# Sheet1.net
KiCad netlist of a schematic drawn in Altium Designer
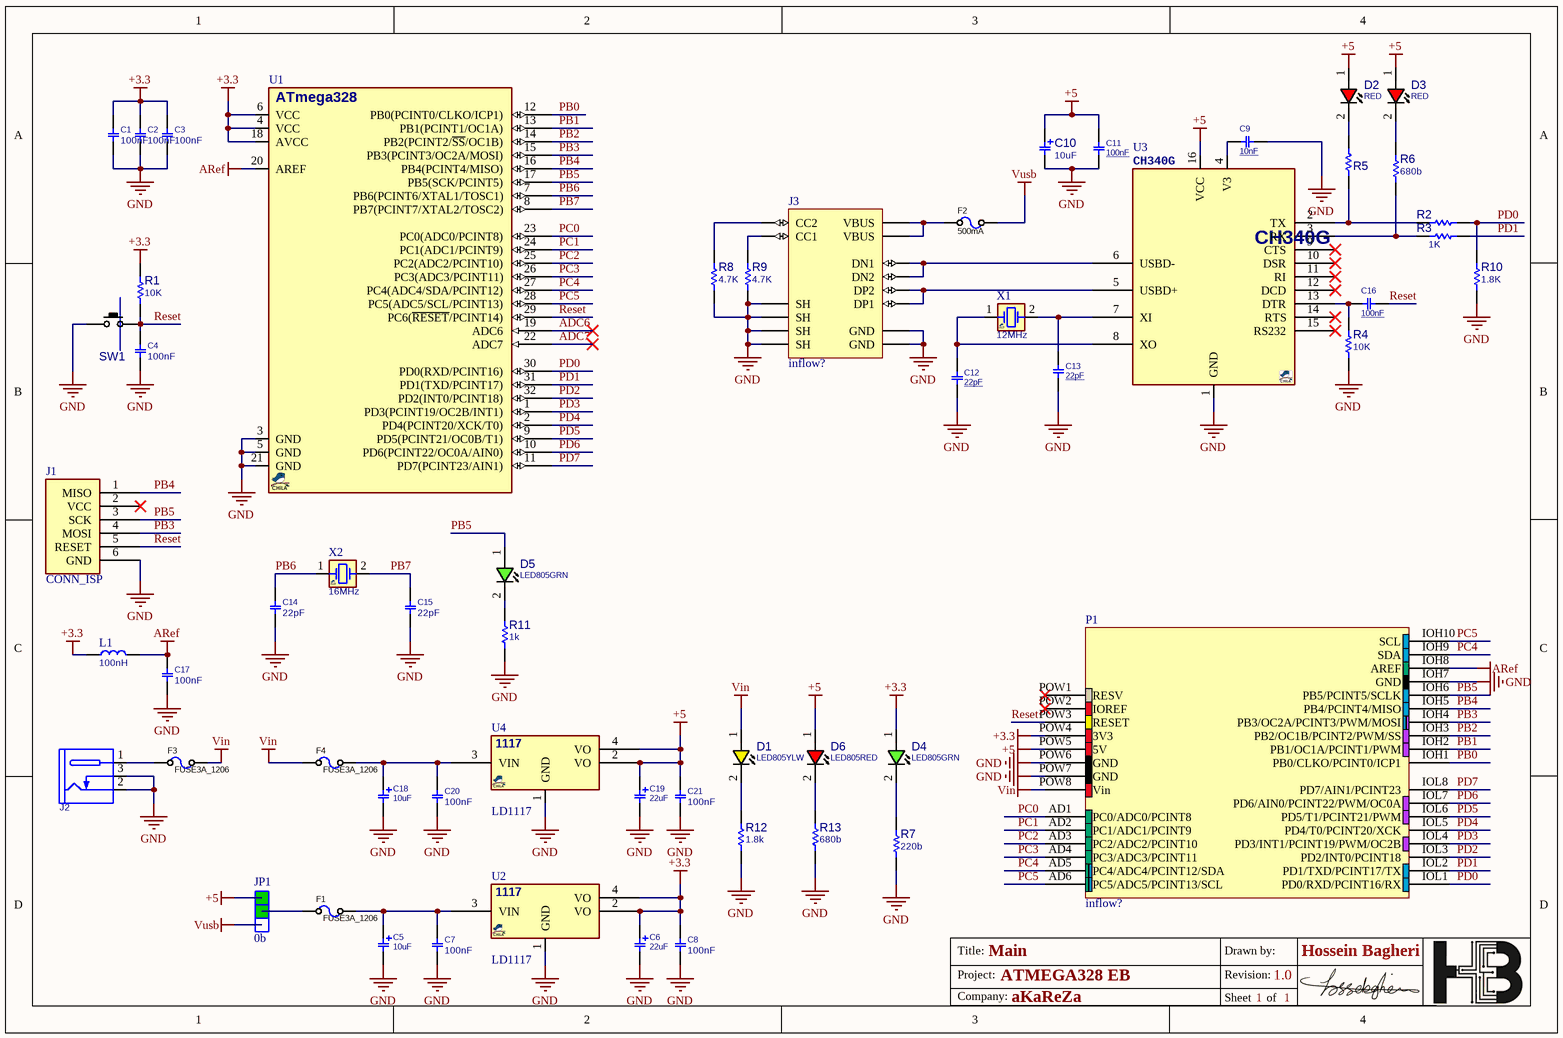
[diagram p0: Sheet1.SchDoc]

(export (version "E")
  (design (tool "Eeschema 10.0.6"))
  (components
    (comp (ref "C1")
      (value "100nF")
      (footprint "C0805")
      (description "CAP, MLCC")
      (fields (field (name "MANF_P#") "MANF_PART#"))
      (libsource (lib "Chila_PCB") (part "CAP_SMD_MLCC_0805"))
    )
    (comp (ref "C2")
      (value "100nF")
      (footprint "C0805")
      (description "CAP, MLCC")
      (fields (field (name "MANF_P#") "MANF_PART#"))
      (libsource (lib "Chila_PCB") (part "CAP_SMD_MLCC_0805"))
    )
    (comp (ref "C3")
      (value "100nF")
      (footprint "C0805")
      (description "CAP, MLCC")
      (fields (field (name "MANF_P#") "MANF_PART#"))
      (libsource (lib "Chila_PCB") (part "CAP_SMD_MLCC_0805"))
    )
    (comp (ref "C4")
      (value "100nF")
      (footprint "C0805")
      (description "CAP, MLCC")
      (fields (field (name "MANF_P#") "MANF_PART#"))
      (libsource (lib "Chila_PCB") (part "CAP_SMD_MLCC_0805"))
    )
    (comp (ref "C5")
      (value "10uF")
      (footprint "C_TN_2012")
      (description "CAP, SMD, TAN")
      (fields (field (name "MANF") "VISHAY") (field (name "MANF_P#") "T55A106M6R3C0300"))
      (libsource (lib "Chila_PCB") (part "CAP_SMD_TAN"))
    )
    (comp (ref "C6")
      (value "22uF")
      (footprint "C_TN_2012")
      (description "CAP, SMD, TAN")
      (fields (field (name "MANF") "VISHAY") (field (name "MANF_P#") "T55A106M6R3C0300"))
      (libsource (lib "Chila_PCB") (part "CAP_SMD_TAN"))
    )
    (comp (ref "C7")
      (value "100nF")
      (footprint "C1206")
      (description "CAP, MLCC")
      (fields (field (name "MANF_P#") "MANF_PART#"))
      (libsource (lib "Chila_PCB") (part "CAP_SMD_MLCC_1206"))
    )
    (comp (ref "C8")
      (value "100nF")
      (footprint "C1206")
      (description "CAP, MLCC")
      (fields (field (name "MANF_P#") "MANF_PART#"))
      (libsource (lib "Chila_PCB") (part "CAP_SMD_MLCC_1206"))
    )
    (comp (ref "C9")
      (value "10nF")
      (footprint "C1206")
      (description "CAP, FILM, 680nF, 16V, Acryl, 20%, 1206")
      (fields (field (name "MANF") "Murata"))
      (libsource (lib "Chila_PCB") (part "CAP_SMD_FILM"))
    )
    (comp (ref "C10")
      (value "10uF")
      (footprint "C_EL_D4L5")
      (description "CAP, SMD, ELEC,")
      (fields (field (name "MANF_P#") "MANF_PART#") (field (name "MANF") "MANF"))
      (libsource (lib "Chila_PCB") (part "CAP_SMD_EL"))
    )
    (comp (ref "C11")
      (value "100nF")
      (footprint "C1206")
      (description "CAP, FILM, 680nF, 16V, Acryl, 20%, 1206")
      (fields (field (name "MANF") "Murata"))
      (libsource (lib "Chila_PCB") (part "CAP_SMD_FILM"))
    )
    (comp (ref "C12")
      (value "22pF")
      (footprint "C1206")
      (description "CAP, FILM, 680nF, 16V, Acryl, 20%, 1206")
      (fields (field (name "MANF") "Murata"))
      (libsource (lib "Chila_PCB") (part "CAP_SMD_FILM"))
    )
    (comp (ref "C13")
      (value "22pF")
      (footprint "C1206")
      (description "CAP, FILM, 680nF, 16V, Acryl, 20%, 1206")
      (fields (field (name "MANF") "Murata"))
      (libsource (lib "Chila_PCB") (part "CAP_SMD_FILM"))
    )
    (comp (ref "C14")
      (value "22pF")
      (footprint "C0805")
      (description "CAP, MLCC")
      (fields (field (name "MANF_P#") "MANF_PART#"))
      (libsource (lib "Chila_PCB") (part "CAP_SMD_MLCC_0805"))
    )
    (comp (ref "C15")
      (value "22pF")
      (footprint "C0805")
      (description "CAP, MLCC")
      (fields (field (name "MANF_P#") "MANF_PART#"))
      (libsource (lib "Chila_PCB") (part "CAP_SMD_MLCC_0805"))
    )
    (comp (ref "C16")
      (value "100nF")
      (footprint "C1206")
      (description "CAP, FILM, 680nF, 16V, Acryl, 20%, 1206")
      (fields (field (name "MANF") "Murata"))
      (libsource (lib "Chila_PCB") (part "CAP_SMD_FILM"))
    )
    (comp (ref "C17")
      (value "100nF")
      (footprint "C0805")
      (description "CAP, MLCC")
      (fields (field (name "MANF_P#") "MANF_PART#"))
      (libsource (lib "Chila_PCB") (part "CAP_SMD_MLCC_0805"))
    )
    (comp (ref "C18")
      (value "10uF")
      (footprint "C_TN_2012")
      (description "CAP, SMD, TAN")
      (fields (field (name "MANF") "VISHAY") (field (name "MANF_P#") "T55A106M6R3C0300"))
      (libsource (lib "Chila_PCB") (part "CAP_SMD_TAN"))
    )
    (comp (ref "C19")
      (value "22uF")
      (footprint "C_TN_2012")
      (description "CAP, SMD, TAN")
      (fields (field (name "MANF") "VISHAY") (field (name "MANF_P#") "T55A106M6R3C0300"))
      (libsource (lib "Chila_PCB") (part "CAP_SMD_TAN"))
    )
    (comp (ref "C20")
      (value "100nF")
      (footprint "C1206")
      (description "CAP, MLCC")
      (fields (field (name "MANF_P#") "MANF_PART#"))
      (libsource (lib "Chila_PCB") (part "CAP_SMD_MLCC_1206"))
    )
    (comp (ref "C21")
      (value "100nF")
      (footprint "C1206")
      (description "CAP, MLCC")
      (fields (field (name "MANF_P#") "MANF_PART#"))
      (libsource (lib "Chila_PCB") (part "CAP_SMD_MLCC_1206"))
    )
    (comp (ref "D1")
      (value "LED805YLW")
      (footprint "LED0805YLW")
      (description "LED, SMD, 0805, YELLOW")
      (fields (field (name "MANF") "MANF") (field (name "MANF_P#") "MANF_PART#"))
      (libsource (lib "Chila_PCB") (part "LED_SMD_0805_YLW"))
    )
    (comp (ref "D2")
      (value "RED")
      (footprint "LED0805RED")
      (description "LED, SMD, 0805, RED")
      (fields (field (name "MANF") "MANF") (field (name "MANF_P#") "MANF_PART#"))
      (libsource (lib "Chila_PCB") (part "LED_SMD_0805_RED"))
    )
    (comp (ref "D3")
      (value "RED")
      (footprint "LED0805RED")
      (description "LED, SMD, 0805, RED")
      (fields (field (name "MANF") "MANF") (field (name "MANF_P#") "MANF_PART#"))
      (libsource (lib "Chila_PCB") (part "LED_SMD_0805_RED"))
    )
    (comp (ref "D4")
      (value "LED805GRN")
      (footprint "LED0805GRN")
      (description "LED, SMD, 0805, GREEN")
      (libsource (lib "Chila_PCB") (part "LED_SMD_0805_GRN"))
    )
    (comp (ref "D5")
      (value "LED805GRN")
      (footprint "LED0805GRN")
      (description "LED, SMD, 0805, GREEN")
      (libsource (lib "Chila_PCB") (part "LED_SMD_0805_GRN"))
    )
    (comp (ref "D6")
      (value "LED805RED")
      (footprint "LED0805RED")
      (description "LED, SMD, 0805, RED")
      (fields (field (name "MANF") "MANF") (field (name "MANF_P#") "MANF_PART#"))
      (libsource (lib "Chila_PCB") (part "LED_SMD_0805_RED"))
    )
    (comp (ref "F1")
      (value "FUSE3A_1206")
      (footprint "F1206")
      (description "Fuse, 3A, 32VDC, 1206, SMD, Slow Blow")
      (fields (field (name "MANF") "Bourns") (field (name "MANF_P#") "SF-1206SP300-2"))
      (libsource (lib "Chila_PCB") (part "FUSE_3A_1206_SLOW"))
    )
    (comp (ref "F2")
      (value "500mA")
      (footprint "F1206")
      (description "Fuse, 3A, 32VDC, 1206, SMD, Slow Blow")
      (fields (field (name "MANF") "Bourns") (field (name "MANF_P#") "SF-1206SP300-2"))
      (libsource (lib "Chila_PCB") (part "FUSE_3A_1206_SLOW"))
    )
    (comp (ref "F3")
      (value "FUSE3A_1206")
      (footprint "F1206")
      (description "Fuse, 3A, 32VDC, 1206, SMD, Slow Blow")
      (fields (field (name "MANF") "Bourns") (field (name "MANF_P#") "SF-1206SP300-2"))
      (libsource (lib "Chila_PCB") (part "FUSE_3A_1206_SLOW"))
    )
    (comp (ref "F4")
      (value "FUSE3A_1206")
      (footprint "F1206")
      (description "Fuse, 3A, 32VDC, 1206, SMD, Slow Blow")
      (fields (field (name "MANF") "Bourns") (field (name "MANF_P#") "SF-1206SP300-2"))
      (libsource (lib "Chila_PCB") (part "FUSE_3A_1206_SLOW"))
    )
    (comp (ref "J1")
      (value "CONN_ISP")
      (footprint "IDC_2X3")
      (description "CONN, ISP, AVR , HEADER BOX")
      (libsource (lib "Chila_PCB") (part "CONN_AVR_ISP_IDC6"))
    )
    (comp (ref "J2")
      (value "DC_POWER_JACK")
      (footprint "JAC_PWR2")
      (description "CONN, PWR JACK DC, PLUG DIAM 2.0MM RA THD")
      (fields
        (field (name "MANF") "CUI STACK")
        (field (name "MANF_P#") "PJ-202A, PJ-002AH, PJ-102AH, KLDX-0202")
      )
      (libsource (lib "Chila_PCB") (part "CONN_PWR_JACKR2"))
    )
    (comp (ref "J3")
      (value "12b")
      (footprint "HRO_TYPE-C-31-M-12 - Extended")
      (description "USB C Female Connector")
      (fields (field (name "INFLOW") "inflow?") (field (name "VALIDATION") "Valid"))
      (libsource (lib "aKaReZa") (part "Con_USB_C"))
    )
    (comp (ref "JP1")
      (value "0b")
      (footprint "jumper selector")
      (description "Jumper Selector")
      (fields (field (name "VALIDATION") "NT"))
      (libsource (lib "aKaReZa") (part "SW_Other_JSelector_Dip"))
    )
    (comp (ref "L1")
      (value "100nH")
      (footprint "L0805")
      (description "INDUCTOR, SMD")
      (fields (field (name "MANF") "EPCOS / TDK") (field (name "MANF_P#") "B82498F3331J"))
      (libsource (lib "Chila_PCB") (part "IND_SMD_330nH_0.2A"))
    )
    (comp (ref "P1")
      (value "UNO")
      (footprint "ARDUINO_UNO_CONNECTOR")
      (description "Arduino UNO Connector")
      (fields (field (name "INFLOW") "inflow?") (field (name "VALIDATION") "NT"))
      (libsource (lib "aKaReZa") (part "Con_Arduino_UNO_Con"))
    )
    (comp (ref "R1")
      (value "10K")
      (footprint "R0805")
      (description "RESISTOR, SMD")
      (libsource (lib "Chila_PCB") (part "RES_SMD_0805"))
    )
    (comp (ref "R2")
      (value "1K")
      (footprint "R0805")
      (description "RESISTOR, SMD")
      (libsource (lib "Chila_PCB") (part "RES_SMD_0805"))
    )
    (comp (ref "R3")
      (value "1K")
      (footprint "R0805")
      (description "RESISTOR, SMD")
      (libsource (lib "Chila_PCB") (part "RES_SMD_0805"))
    )
    (comp (ref "R4")
      (value "10K")
      (footprint "R0805")
      (description "RESISTOR, SMD")
      (libsource (lib "Chila_PCB") (part "RES_SMD_0805"))
    )
    (comp (ref "R5")
      (value "680b")
      (footprint "R0805")
      (description "RESISTOR, SMD")
      (libsource (lib "Chila_PCB") (part "RES_SMD_0805"))
    )
    (comp (ref "R6")
      (value "680b")
      (footprint "R0805")
      (description "RESISTOR, SMD")
      (libsource (lib "Chila_PCB") (part "RES_SMD_0805"))
    )
    (comp (ref "R7")
      (value "220b")
      (footprint "R0805")
      (description "RESISTOR, SMD")
      (libsource (lib "Chila_PCB") (part "RES_SMD_0805"))
    )
    (comp (ref "R8")
      (value "4.7K")
      (footprint "R0805")
      (description "RESISTOR, SMD")
      (libsource (lib "Chila_PCB") (part "RES_SMD_0805"))
    )
    (comp (ref "R9")
      (value "4.7K")
      (footprint "R0805")
      (description "RESISTOR, SMD")
      (libsource (lib "Chila_PCB") (part "RES_SMD_0805"))
    )
    (comp (ref "R10")
      (value "1.8K")
      (footprint "R0805")
      (description "RESISTOR, SMD")
      (libsource (lib "Chila_PCB") (part "RES_SMD_0805"))
    )
    (comp (ref "R11")
      (value "1k")
      (footprint "R0805")
      (description "RESISTOR, SMD")
      (libsource (lib "Chila_PCB") (part "RES_SMD_0805"))
    )
    (comp (ref "R12")
      (value "1.8k")
      (footprint "R0805")
      (description "RESISTOR, SMD")
      (libsource (lib "Chila_PCB") (part "RES_SMD_0805"))
    )
    (comp (ref "R13")
      (value "680b")
      (footprint "R0805")
      (description "RESISTOR, SMD")
      (libsource (lib "Chila_PCB") (part "RES_SMD_0805"))
    )
    (comp (ref "SW1")
      (value "PUSHBUTTON")
      (footprint "SWPBS_SPST_6X3X2")
      (description "SWITCH, PUSH BUTTON, TACTILE, SMD, SPST, 6X3.5X2.5mm")
      (fields (field (name "MANF") "C&K") (field (name "MANF_P#") "RS-282G05A3-SM RT"))
      (libsource (lib "Chila_PCB") (part "SWPBS_SPST_6X3X2_RS282"))
    )
    (comp (ref "U1")
      (value "ATMEGA328")
      (footprint "QFG80_32")
      (description "MCU, AVR, 8-Bit, 16KB, 1KB RAM, 20MHz")
      (fields (field (name "MANF_P#") "ATMEGA328-AU") (field (name "MANF") "ATMEL/MICROCHIP"))
      (libsource (lib "Chila_PCB") (part "ATMEGA328_QFP32"))
    )
    (comp (ref "U2")
      (value "LD1117")
      (footprint "SOT223_4")
      (description "REG, Linear, LDO1V, 0.8A, SOT-223")
      (fields
        (field (name "MANF_P#") "LD1117, LM1117, AMS1117, TLV1117, REG1117, NCP1117, LT1117, SPX1117")
        (field (name "MANF") "TI, ON, ST")
      )
      (libsource (lib "Chila_PCB") (part "VREG_1117_SOT223"))
    )
    (comp (ref "U3")
      (value "CH340G")
      (footprint "SO_16")
      (description "USB-UART")
      (libsource (lib "Chila_PCB") (part "CH340G_SOP16"))
    )
    (comp (ref "U4")
      (value "LD1117")
      (footprint "SOT223_4")
      (description "REG, Linear, LDO1V, 0.8A, SOT-223")
      (fields
        (field (name "MANF_P#") "LD1117, LM1117, AMS1117, TLV1117, REG1117, NCP1117, LT1117, SPX1117")
        (field (name "MANF") "TI, ON, ST")
      )
      (libsource (lib "Chila_PCB") (part "VREG_1117_SOT223"))
    )
    (comp (ref "X1")
      (value "12MHz")
      (footprint "XTL_2_11X5")
      (description "Crystal MOST POPULAR ABL HC49 PACKAGE")
      (fields (field (name "MANF") "ABRACON") (field (name "MANF_P#") "ABLS-8.000MHZ-B4-T"))
      (libsource (lib "Chila_PCB") (part "XTL_2_HC49_8MHz_SMD"))
    )
    (comp (ref "X2")
      (value "16MHz")
      (footprint "XTL_2_11X5")
      (description "Crystal MOST POPULAR ABL HC49 PACKAGE")
      (libsource (lib "Chila_PCB") (part "XTL_2_HC49_SMD"))
    )
  )
  (nets
    (net (code "1") (name "+3.3") (class "Default")
      (node (ref "C1") (pin "2") (pinfunction "2_2") (pintype "passive"))
      (node (ref "C2") (pin "2") (pinfunction "2_2") (pintype "passive"))
      (node (ref "C3") (pin "2") (pinfunction "2_2") (pintype "passive"))
      (node (ref "C6") (pin "1") (pinfunction "1_1") (pintype "passive"))
      (node (ref "C8") (pin "2") (pinfunction "2_2") (pintype "passive"))
      (node (ref "D4") (pin "1") (pinfunction "ANODE_1") (pintype "passive"))
      (node (ref "L1") (pin "1") (pinfunction "1_1") (pintype "passive"))
      (node (ref "P1") (pin "POW4") (pinfunction "3V3_POW4") (pintype "passive"))
      (node (ref "R1") (pin "1") (pinfunction "1_1") (pintype "passive"))
      (node (ref "U1") (pin "18") (pinfunction "AVCC_18") (pintype "power_in"))
      (node (ref "U1") (pin "4") (pinfunction "VCC_4") (pintype "power_in"))
      (node (ref "U1") (pin "6") (pinfunction "VCC_6") (pintype "power_in"))
      (node (ref "U2") (pin "2") (pinfunction "VO_2") (pintype "passive"))
      (node (ref "U2") (pin "4") (pinfunction "VO_4") (pintype "passive"))
    )
    (net (code "2") (name "+5") (class "Default")
      (node (ref "C10") (pin "1") (pinfunction "1_1") (pintype "passive"))
      (node (ref "C11") (pin "2") (pinfunction "2_2") (pintype "passive"))
      (node (ref "C19") (pin "1") (pinfunction "1_1") (pintype "passive"))
      (node (ref "C21") (pin "2") (pinfunction "2_2") (pintype "passive"))
      (node (ref "D2") (pin "1") (pinfunction "ANODE_1") (pintype "passive"))
      (node (ref "D3") (pin "1") (pinfunction "ANODE_1") (pintype "passive"))
      (node (ref "D6") (pin "1") (pinfunction "ANODE_1") (pintype "passive"))
      (node (ref "JP1") (pin "1") (pinfunction "1_1") (pintype "passive"))
      (node (ref "P1") (pin "POW5") (pinfunction "5V_POW5") (pintype "passive"))
      (node (ref "U3") (pin "16") (pinfunction "VCC_16") (pintype "passive"))
      (node (ref "U4") (pin "2") (pinfunction "VO_2") (pintype "passive"))
      (node (ref "U4") (pin "4") (pinfunction "VO_4") (pintype "passive"))
    )
    (net (code "3") (name "/ADC6") (class "Default")
      (node (ref "U1") (pin "19") (pinfunction "ADC6_19") (pintype "input+no_connect"))
    )
    (net (code "4") (name "/ADC7") (class "Default")
      (node (ref "U1") (pin "22") (pinfunction "ADC7_22") (pintype "input+no_connect"))
    )
    (net (code "5") (name "/PB0") (class "Default")
      (node (ref "P1") (pin "IOH1") (pinfunction "PB0/CLKO/PCINT0/ICP1_IOH1") (pintype "passive"))
      (node (ref "U1") (pin "12") (pinfunction "PB0(PCINT0/CLKO/ICP1)_12") (pintype "bidirectional"))
    )
    (net (code "6") (name "/PB1") (class "Default")
      (node (ref "P1") (pin "IOH2") (pinfunction "PB1/OC1A/PCINT1/PWM_IOH2") (pintype "passive"))
      (node (ref "U1") (pin "13") (pinfunction "PB1(PCINT1/OC1A)_13") (pintype "bidirectional"))
    )
    (net (code "7") (name "/PB2") (class "Default")
      (node (ref "P1") (pin "IOH3") (pinfunction "PB2/OC1B/PCINT2/PWM/SS_IOH3") (pintype "passive"))
      (node (ref "U1") (pin "14") (pinfunction "PB2(PCINT2/~{SS}/OC1B)_14") (pintype "bidirectional"))
    )
    (net (code "8") (name "/PB3") (class "Default")
      (node (ref "J1") (pin "4") (pinfunction "MOSI_4") (pintype "passive"))
      (node (ref "P1") (pin "IOH4") (pinfunction "PB3/OC2A/PCINT3/PWM/MOSI_IOH4") (pintype "passive"))
      (node (ref "U1") (pin "15") (pinfunction "PB3(PCINT3/OC2A/MOSI)_15") (pintype "bidirectional"))
    )
    (net (code "9") (name "/PB4") (class "Default")
      (node (ref "J1") (pin "1") (pinfunction "MISO_1") (pintype "passive"))
      (node (ref "P1") (pin "IOH5") (pinfunction "PB4/PCINT4/MISO_IOH5") (pintype "passive"))
      (node (ref "U1") (pin "16") (pinfunction "PB4(PCINT4/MISO)_16") (pintype "bidirectional"))
    )
    (net (code "10") (name "/PB5") (class "Default")
      (node (ref "D5") (pin "1") (pinfunction "ANODE_1") (pintype "passive"))
      (node (ref "J1") (pin "3") (pinfunction "SCK_3") (pintype "passive"))
      (node (ref "P1") (pin "IOH6") (pinfunction "PB5/PCINT5/SCLK_IOH6") (pintype "passive"))
      (node (ref "U1") (pin "17") (pinfunction "PB5(SCK/PCINT5)_17") (pintype "bidirectional"))
    )
    (net (code "11") (name "/PB6") (class "Default")
      (node (ref "C14") (pin "2") (pinfunction "2_2") (pintype "passive"))
      (node (ref "U1") (pin "7") (pinfunction "PB6(PCINT6/XTAL1/TOSC1)_7") (pintype "bidirectional"))
      (node (ref "X2") (pin "1") (pinfunction "OSC1_1") (pintype "passive"))
    )
    (net (code "12") (name "/PB7") (class "Default")
      (node (ref "C15") (pin "2") (pinfunction "2_2") (pintype "passive"))
      (node (ref "U1") (pin "8") (pinfunction "PB7(PCINT7/XTAL2/TOSC2)_8") (pintype "bidirectional"))
      (node (ref "X2") (pin "2") (pinfunction "OSC2_2") (pintype "passive"))
    )
    (net (code "13") (name "/PC0") (class "Default")
      (node (ref "P1") (pin "AD1") (pinfunction "PC0/ADC0/PCINT8_AD1") (pintype "passive"))
      (node (ref "U1") (pin "23") (pinfunction "PC0(ADC0/PCINT8)_23") (pintype "bidirectional"))
    )
    (net (code "14") (name "/PC1") (class "Default")
      (node (ref "P1") (pin "AD2") (pinfunction "PC1/ADC1/PCINT9_AD2") (pintype "passive"))
      (node (ref "U1") (pin "24") (pinfunction "PC1(ADC1/PCINT9)_24") (pintype "bidirectional"))
    )
    (net (code "15") (name "/PC2") (class "Default")
      (node (ref "P1") (pin "AD3") (pinfunction "PC2/ADC2/PCINT10_AD3") (pintype "passive"))
      (node (ref "U1") (pin "25") (pinfunction "PC2(ADC2/PCINT10)_25") (pintype "bidirectional"))
    )
    (net (code "16") (name "/PC3") (class "Default")
      (node (ref "P1") (pin "AD4") (pinfunction "PC3/ADC3/PCINT11_AD4") (pintype "passive"))
      (node (ref "U1") (pin "26") (pinfunction "PC3(ADC3/PCINT11)_26") (pintype "bidirectional"))
    )
    (net (code "17") (name "/PC4") (class "Default")
      (node (ref "P1") (pin "AD5") (pinfunction "PC4/ADC4/PCINT12/SDA_AD5") (pintype "passive"))
      (node (ref "P1") (pin "IOH9") (pinfunction "SDA_IOH9") (pintype "passive"))
      (node (ref "U1") (pin "27") (pinfunction "PC4(ADC4/SDA/PCINT12)_27") (pintype "bidirectional"))
    )
    (net (code "18") (name "/PC5") (class "Default")
      (node (ref "P1") (pin "AD6") (pinfunction "PC5/ADC5/PCINT13/SCL_AD6") (pintype "passive"))
      (node (ref "P1") (pin "IOH10") (pinfunction "SCL_IOH10") (pintype "passive"))
      (node (ref "U1") (pin "28") (pinfunction "PC5(ADC5/SCL/PCINT13)_28") (pintype "bidirectional"))
    )
    (net (code "19") (name "/PD0") (class "Default")
      (node (ref "P1") (pin "IOL1") (pinfunction "PD0/RXD/PCINT16/RX_IOL1") (pintype "passive"))
      (node (ref "R10") (pin "2") (pinfunction "2_2") (pintype "passive"))
      (node (ref "R2") (pin "2") (pinfunction "2_2") (pintype "passive"))
      (node (ref "U1") (pin "30") (pinfunction "PD0(RXD/PCINT16)_30") (pintype "bidirectional"))
    )
    (net (code "20") (name "/PD1") (class "Default")
      (node (ref "P1") (pin "IOL2") (pinfunction "PD1/TXD/PCINT17/TX_IOL2") (pintype "passive"))
      (node (ref "R3") (pin "2") (pinfunction "2_2") (pintype "passive"))
      (node (ref "U1") (pin "31") (pinfunction "PD1(TXD/PCINT17)_31") (pintype "bidirectional"))
    )
    (net (code "21") (name "/PD2") (class "Default")
      (node (ref "P1") (pin "IOL3") (pinfunction "PD2/INT0/PCINT18_IOL3") (pintype "passive"))
      (node (ref "U1") (pin "32") (pinfunction "PD2(INT0/PCINT18)_32") (pintype "bidirectional"))
    )
    (net (code "22") (name "/PD3") (class "Default")
      (node (ref "P1") (pin "IOL4") (pinfunction "PD3/INT1/PCINT19/PWM/OC2B_IOL4") (pintype "passive"))
      (node (ref "U1") (pin "1") (pinfunction "PD3(PCINT19/OC2B/INT1)_1") (pintype "bidirectional"))
    )
    (net (code "23") (name "/PD4") (class "Default")
      (node (ref "P1") (pin "IOL5") (pinfunction "PD4/T0/PCINT20/XCK_IOL5") (pintype "passive"))
      (node (ref "U1") (pin "2") (pinfunction "PD4(PCINT20/XCK/T0)_2") (pintype "bidirectional"))
    )
    (net (code "24") (name "/PD5") (class "Default")
      (node (ref "P1") (pin "IOL6") (pinfunction "PD5/T1/PCINT21/PWM_IOL6") (pintype "passive"))
      (node (ref "U1") (pin "9") (pinfunction "PD5(PCINT21/OC0B/T1)_9") (pintype "bidirectional"))
    )
    (net (code "25") (name "/PD6") (class "Default")
      (node (ref "P1") (pin "IOL7") (pinfunction "PD6/AIN0/PCINT22/PWM/OC0A_IOL7") (pintype "passive"))
      (node (ref "U1") (pin "10") (pinfunction "PD6(PCINT22/OC0A/AIN0)_10") (pintype "bidirectional"))
    )
    (net (code "26") (name "/PD7") (class "Default")
      (node (ref "P1") (pin "IOL8") (pinfunction "PD7/AIN1/PCINT23_IOL8") (pintype "passive"))
      (node (ref "U1") (pin "11") (pinfunction "PD7(PCINT23/AIN1)_11") (pintype "bidirectional"))
    )
    (net (code "27") (name "/Reset") (class "Default")
      (node (ref "C16") (pin "1") (pinfunction "1_1") (pintype "passive"))
      (node (ref "C4") (pin "2") (pinfunction "2_2") (pintype "passive"))
      (node (ref "J1") (pin "5") (pinfunction "RESET_5") (pintype "passive"))
      (node (ref "P1") (pin "POW3") (pinfunction "RESET_POW3") (pintype "passive"))
      (node (ref "R1") (pin "2") (pinfunction "2_2") (pintype "passive"))
      (node (ref "SW1") (pin "2") (pinfunction "P3_2") (pintype "passive"))
      (node (ref "U1") (pin "29") (pinfunction "PC6(~{RESET}/PCINT14)_29") (pintype "bidirectional"))
    )
    (net (code "28") (name "ARef") (class "Default")
      (node (ref "C17") (pin "2") (pinfunction "2_2") (pintype "passive"))
      (node (ref "L1") (pin "2") (pinfunction "2_2") (pintype "passive"))
      (node (ref "P1") (pin "IOH8") (pinfunction "AREF_IOH8") (pintype "passive"))
      (node (ref "U1") (pin "20") (pinfunction "AREF_20") (pintype "passive"))
    )
    (net (code "29") (name "GND") (class "Default")
      (node (ref "C1") (pin "1") (pinfunction "1_1") (pintype "passive"))
      (node (ref "C10") (pin "2") (pinfunction "2_2") (pintype "passive"))
      (node (ref "C11") (pin "1") (pinfunction "1_1") (pintype "passive"))
      (node (ref "C12") (pin "1") (pinfunction "1_1") (pintype "passive"))
      (node (ref "C13") (pin "1") (pinfunction "1_1") (pintype "passive"))
      (node (ref "C14") (pin "1") (pinfunction "1_1") (pintype "passive"))
      (node (ref "C15") (pin "1") (pinfunction "1_1") (pintype "passive"))
      (node (ref "C17") (pin "1") (pinfunction "1_1") (pintype "passive"))
      (node (ref "C18") (pin "2") (pinfunction "2_2") (pintype "passive"))
      (node (ref "C19") (pin "2") (pinfunction "2_2") (pintype "passive"))
      (node (ref "C2") (pin "1") (pinfunction "1_1") (pintype "passive"))
      (node (ref "C20") (pin "1") (pinfunction "1_1") (pintype "passive"))
      (node (ref "C21") (pin "1") (pinfunction "1_1") (pintype "passive"))
      (node (ref "C3") (pin "1") (pinfunction "1_1") (pintype "passive"))
      (node (ref "C4") (pin "1") (pinfunction "1_1") (pintype "passive"))
      (node (ref "C5") (pin "2") (pinfunction "2_2") (pintype "passive"))
      (node (ref "C6") (pin "2") (pinfunction "2_2") (pintype "passive"))
      (node (ref "C7") (pin "1") (pinfunction "1_1") (pintype "passive"))
      (node (ref "C8") (pin "1") (pinfunction "1_1") (pintype "passive"))
      (node (ref "C9") (pin "1") (pinfunction "1_1") (pintype "passive"))
      (node (ref "J1") (pin "6") (pinfunction "GND_6") (pintype "passive"))
      (node (ref "J2") (pin "2") (pinfunction "SLEEVE_2") (pintype "power_in"))
      (node (ref "J2") (pin "3") (pinfunction "INSERTION_DET_3") (pintype "power_in"))
      (node (ref "J3") (pin "A1_B12") (pinfunction "GND_A1_B12") (pintype "power_in"))
      (node (ref "J3") (pin "B1_A12") (pinfunction "GND_B1_A12") (pintype "power_in"))
      (node (ref "J3") (pin "S1") (pinfunction "SH_S1") (pintype "passive"))
      (node (ref "J3") (pin "S2") (pinfunction "SH_S2") (pintype "passive"))
      (node (ref "J3") (pin "S3") (pinfunction "SH_S3") (pintype "passive"))
      (node (ref "J3") (pin "S4") (pinfunction "SH_S4") (pintype "passive"))
      (node (ref "P1") (pin "IOH7") (pinfunction "GND_IOH7") (pintype "passive"))
      (node (ref "P1") (pin "POW6") (pinfunction "GND_POW6") (pintype "passive"))
      (node (ref "P1") (pin "POW7") (pinfunction "GND_POW7") (pintype "passive"))
      (node (ref "R10") (pin "1") (pinfunction "1_1") (pintype "passive"))
      (node (ref "R11") (pin "1") (pinfunction "1_1") (pintype "passive"))
      (node (ref "R12") (pin "1") (pinfunction "1_1") (pintype "passive"))
      (node (ref "R13") (pin "1") (pinfunction "1_1") (pintype "passive"))
      (node (ref "R4") (pin "1") (pinfunction "1_1") (pintype "passive"))
      (node (ref "R7") (pin "1") (pinfunction "1_1") (pintype "passive"))
      (node (ref "R8") (pin "1") (pinfunction "1_1") (pintype "passive"))
      (node (ref "R9") (pin "1") (pinfunction "1_1") (pintype "passive"))
      (node (ref "SW1") (pin "1") (pinfunction "P1_1") (pintype "passive"))
      (node (ref "U1") (pin "21") (pinfunction "GND_21") (pintype "power_in"))
      (node (ref "U1") (pin "3") (pinfunction "GND_3") (pintype "power_in"))
      (node (ref "U1") (pin "5") (pinfunction "GND_5") (pintype "power_in"))
      (node (ref "U2") (pin "1") (pinfunction "GND_1") (pintype "passive"))
      (node (ref "U3") (pin "1") (pinfunction "GND_1") (pintype "passive"))
      (node (ref "U4") (pin "1") (pinfunction "GND_1") (pintype "passive"))
    )
    (net (code "30") (name "Net-(D1-CATHODE)") (class "Default")
      (node (ref "D1") (pin "2") (pinfunction "CATHODE_2") (pintype "passive"))
      (node (ref "R12") (pin "2") (pinfunction "2_2") (pintype "passive"))
    )
    (net (code "31") (name "Net-(D2-CATHODE)") (class "Default")
      (node (ref "D2") (pin "2") (pinfunction "CATHODE_2") (pintype "passive"))
      (node (ref "R5") (pin "2") (pinfunction "2_2") (pintype "passive"))
    )
    (net (code "32") (name "Net-(D3-CATHODE)") (class "Default")
      (node (ref "D3") (pin "2") (pinfunction "CATHODE_2") (pintype "passive"))
      (node (ref "R6") (pin "2") (pinfunction "2_2") (pintype "passive"))
    )
    (net (code "33") (name "Net-(D4-CATHODE)") (class "Default")
      (node (ref "D4") (pin "2") (pinfunction "CATHODE_2") (pintype "passive"))
      (node (ref "R7") (pin "2") (pinfunction "2_2") (pintype "passive"))
    )
    (net (code "34") (name "Net-(D5-CATHODE)") (class "Default")
      (node (ref "D5") (pin "2") (pinfunction "CATHODE_2") (pintype "passive"))
      (node (ref "R11") (pin "2") (pinfunction "2_2") (pintype "passive"))
    )
    (net (code "35") (name "Net-(D6-CATHODE)") (class "Default")
      (node (ref "D6") (pin "2") (pinfunction "CATHODE_2") (pintype "passive"))
      (node (ref "R13") (pin "2") (pinfunction "2_2") (pintype "passive"))
    )
    (net (code "36") (name "Net-(F1-Pad1)") (class "Default")
      (node (ref "F1") (pin "1") (pinfunction "1_1") (pintype "passive"))
      (node (ref "JP1") (pin "2") (pinfunction "2_2") (pintype "passive"))
    )
    (net (code "37") (name "Net-(F2-Pad1)") (class "Default")
      (node (ref "F2") (pin "1") (pinfunction "1_1") (pintype "passive"))
      (node (ref "J3") (pin "A4_B9") (pinfunction "VBUS_A4_B9") (pintype "power_in"))
      (node (ref "J3") (pin "B4_A9") (pinfunction "VBUS_B4_A9") (pintype "power_in"))
    )
    (net (code "38") (name "Net-(J2-TIP)") (class "Default")
      (node (ref "F3") (pin "1") (pinfunction "1_1") (pintype "passive"))
      (node (ref "J2") (pin "1") (pinfunction "TIP_1") (pintype "power_in"))
    )
    (net (code "39") (name "Net-(J3-CC1)") (class "Default")
      (node (ref "J3") (pin "A5") (pinfunction "CC1_A5") (pintype "bidirectional"))
      (node (ref "R9") (pin "2") (pinfunction "2_2") (pintype "passive"))
    )
    (net (code "40") (name "Net-(J3-CC2)") (class "Default")
      (node (ref "J3") (pin "B5") (pinfunction "CC2_B5") (pintype "bidirectional"))
      (node (ref "R8") (pin "2") (pinfunction "2_2") (pintype "passive"))
    )
    (net (code "41") (name "Net-(J3-DN1)") (class "Default")
      (node (ref "J3") (pin "A7") (pinfunction "DN1_A7") (pintype "bidirectional"))
      (node (ref "J3") (pin "B7") (pinfunction "DN2_B7") (pintype "bidirectional"))
      (node (ref "U3") (pin "6") (pinfunction "USBD-_6") (pintype "passive"))
    )
    (net (code "42") (name "Net-(J3-DP1)") (class "Default")
      (node (ref "J3") (pin "A6") (pinfunction "DP1_A6") (pintype "bidirectional"))
      (node (ref "J3") (pin "B6") (pinfunction "DP2_B6") (pintype "bidirectional"))
      (node (ref "U3") (pin "5") (pinfunction "USBD+_5") (pintype "passive"))
    )
    (net (code "43") (name "Net-(U2-VIN)") (class "Default")
      (node (ref "C5") (pin "1") (pinfunction "1_1") (pintype "passive"))
      (node (ref "C7") (pin "2") (pinfunction "2_2") (pintype "passive"))
      (node (ref "F1") (pin "2") (pinfunction "2_2") (pintype "passive"))
      (node (ref "U2") (pin "3") (pinfunction "VIN_3") (pintype "passive"))
    )
    (net (code "44") (name "Net-(U3-DTR)") (class "Default")
      (node (ref "C16") (pin "2") (pinfunction "2_2") (pintype "passive"))
      (node (ref "R4") (pin "2") (pinfunction "2_2") (pintype "passive"))
      (node (ref "U3") (pin "13") (pinfunction "DTR_13") (pintype "passive"))
    )
    (net (code "45") (name "Net-(U3-RX)") (class "Default")
      (node (ref "R3") (pin "1") (pinfunction "1_1") (pintype "passive"))
      (node (ref "R6") (pin "1") (pinfunction "1_1") (pintype "passive"))
      (node (ref "U3") (pin "3") (pinfunction "RX_3") (pintype "passive"))
    )
    (net (code "46") (name "Net-(U3-TX)") (class "Default")
      (node (ref "R2") (pin "1") (pinfunction "1_1") (pintype "passive"))
      (node (ref "R5") (pin "1") (pinfunction "1_1") (pintype "passive"))
      (node (ref "U3") (pin "2") (pinfunction "TX_2") (pintype "passive"))
    )
    (net (code "47") (name "Net-(U3-V3)") (class "Default")
      (node (ref "C9") (pin "2") (pinfunction "2_2") (pintype "passive"))
      (node (ref "U3") (pin "4") (pinfunction "V3_4") (pintype "passive"))
    )
    (net (code "48") (name "Net-(U3-XI)") (class "Default")
      (node (ref "C13") (pin "2") (pinfunction "2_2") (pintype "passive"))
      (node (ref "U3") (pin "7") (pinfunction "XI_7") (pintype "passive"))
      (node (ref "X1") (pin "2") (pinfunction "OSC2_2") (pintype "passive"))
    )
    (net (code "49") (name "Net-(U3-XO)") (class "Default")
      (node (ref "C12") (pin "2") (pinfunction "2_2") (pintype "passive"))
      (node (ref "U3") (pin "8") (pinfunction "XO_8") (pintype "passive"))
      (node (ref "X1") (pin "1") (pinfunction "OSC1_1") (pintype "passive"))
    )
    (net (code "50") (name "Net-(U4-VIN)") (class "Default")
      (node (ref "C18") (pin "1") (pinfunction "1_1") (pintype "passive"))
      (node (ref "C20") (pin "2") (pinfunction "2_2") (pintype "passive"))
      (node (ref "F4") (pin "2") (pinfunction "2_2") (pintype "passive"))
      (node (ref "U4") (pin "3") (pinfunction "VIN_3") (pintype "passive"))
    )
    (net (code "51") (name "Vin") (class "Default")
      (node (ref "D1") (pin "1") (pinfunction "ANODE_1") (pintype "passive"))
      (node (ref "F3") (pin "2") (pinfunction "2_2") (pintype "passive"))
      (node (ref "F4") (pin "1") (pinfunction "1_1") (pintype "passive"))
      (node (ref "P1") (pin "POW8") (pinfunction "Vin_POW8") (pintype "passive"))
    )
    (net (code "52") (name "Vusb") (class "Default")
      (node (ref "F2") (pin "2") (pinfunction "2_2") (pintype "passive"))
      (node (ref "JP1") (pin "3") (pinfunction "3_3") (pintype "passive"))
    )
    (net (code "53") (name "unconnected-(J1-VCC-Pad2)") (class "Default")
      (node (ref "J1") (pin "2") (pinfunction "VCC_2") (pintype "passive+no_connect"))
    )
    (net (code "54") (name "unconnected-(P1-IOREF-PadPOW2)") (class "Default")
      (node (ref "P1") (pin "POW2") (pinfunction "IOREF_POW2") (pintype "passive+no_connect"))
    )
    (net (code "55") (name "unconnected-(P1-RESV-PadPOW1)") (class "Default")
      (node (ref "P1") (pin "POW1") (pinfunction "RESV_POW1") (pintype "passive+no_connect"))
    )
    (net (code "56") (name "unconnected-(U3-CTS-Pad9)") (class "Default")
      (node (ref "U3") (pin "9") (pinfunction "CTS_9") (pintype "passive+no_connect"))
    )
    (net (code "57") (name "unconnected-(U3-DCD-Pad12)") (class "Default")
      (node (ref "U3") (pin "12") (pinfunction "DCD_12") (pintype "passive+no_connect"))
    )
    (net (code "58") (name "unconnected-(U3-DSR-Pad10)") (class "Default")
      (node (ref "U3") (pin "10") (pinfunction "DSR_10") (pintype "passive+no_connect"))
    )
    (net (code "59") (name "unconnected-(U3-RI-Pad11)") (class "Default")
      (node (ref "U3") (pin "11") (pinfunction "RI_11") (pintype "passive+no_connect"))
    )
    (net (code "60") (name "unconnected-(U3-RS232-Pad15)") (class "Default")
      (node (ref "U3") (pin "15") (pinfunction "RS232_15") (pintype "passive+no_connect"))
    )
    (net (code "61") (name "unconnected-(U3-RTS-Pad14)") (class "Default")
      (node (ref "U3") (pin "14") (pinfunction "RTS_14") (pintype "passive+no_connect"))
    )
  )
)
